# potentiometer_for_5_pin_v1.net
KiCad netlist of a schematic drawn in EAGLE
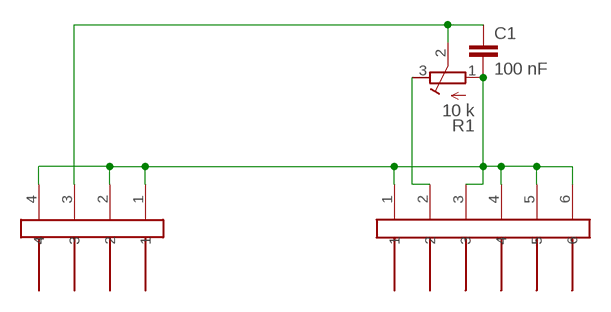
[diagram p0: schematic, sheet 1]

(export (version "E")
  (design (tool "Eeschema 10.0.6"))
  (components
    (comp (ref "C1")
      (value "100 nF")
      (footprint "eagle-import:C0805")
      (libsource (lib "eagle-import") (part "C-EUC0805"))
    )
    (comp (ref "R1")
      (value "10 k")
      (footprint "eagle-import:R-TRIM")
      (libsource (lib "eagle-import") (part "R-TRIM"))
    )
    (comp (ref "U$8")
      (value "JUMPER6M")
      (footprint "eagle-import:JUMPER6M")
      (libsource (lib "eagle-import") (part "JUMPER6M"))
    )
    (comp (ref "U$9")
      (value "JUMPER4M")
      (footprint "eagle-import:JUMPER4M")
      (libsource (lib "eagle-import") (part "JUMPER4M"))
    )
  )
  (nets
    (net (code "1") (name "Net-(R1-A)") (class "Default")
      (node (ref "R1") (pin "3") (pinfunction "A_3") (pintype "passive"))
      (node (ref "U$8") (pin "2") (pinfunction "2_2") (pintype "bidirectional"))
    )
    (net (code "2") (name "Net-(R1-E)") (class "Default")
      (node (ref "C1") (pin "2") (pinfunction "2_2") (pintype "passive"))
      (node (ref "R1") (pin "1") (pinfunction "E_1") (pintype "passive"))
      (node (ref "U$8") (pin "1") (pinfunction "1_1") (pintype "bidirectional"))
      (node (ref "U$8") (pin "3") (pinfunction "3_3") (pintype "bidirectional"))
      (node (ref "U$8") (pin "4") (pinfunction "4_4") (pintype "bidirectional"))
      (node (ref "U$8") (pin "5") (pinfunction "5_5") (pintype "bidirectional"))
      (node (ref "U$8") (pin "6") (pinfunction "6_6") (pintype "bidirectional"))
      (node (ref "U$9") (pin "1") (pinfunction "1_1") (pintype "bidirectional"))
      (node (ref "U$9") (pin "2") (pinfunction "2_2") (pintype "bidirectional"))
      (node (ref "U$9") (pin "4") (pinfunction "4_4") (pintype "bidirectional"))
    )
    (net (code "3") (name "Net-(R1-S)") (class "Default")
      (node (ref "C1") (pin "1") (pinfunction "1_1") (pintype "passive"))
      (node (ref "R1") (pin "2") (pinfunction "S_2") (pintype "passive"))
      (node (ref "U$9") (pin "3") (pinfunction "3_3") (pintype "bidirectional"))
    )
  )
)
